# CndyShield.net
KiCad netlist of a schematic drawn in EAGLE
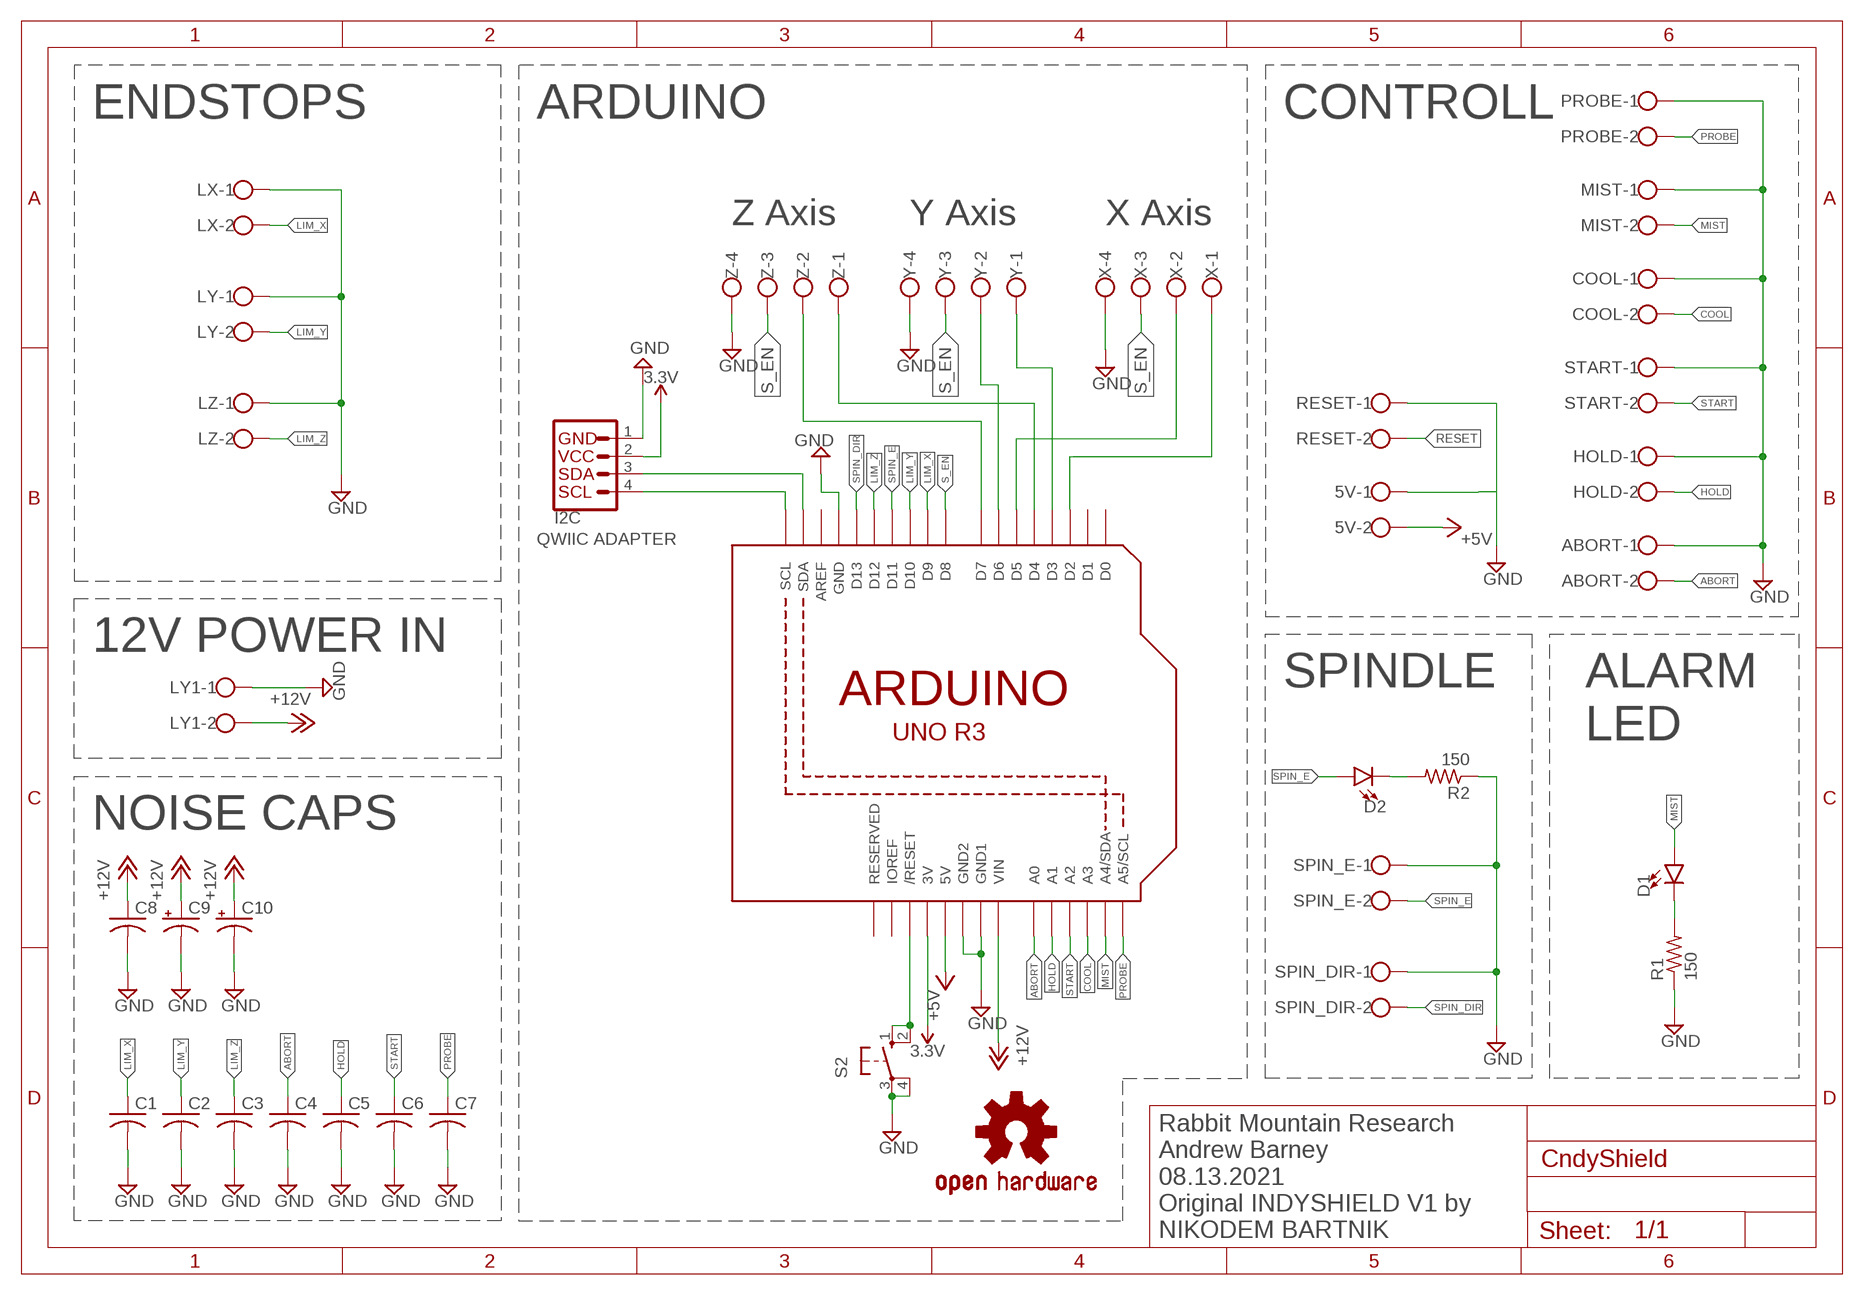
[diagram p0: schematic, sheet 1]

(export (version "E")
  (design (tool "Eeschema 10.0.6"))
  (components
    (comp (ref "5V")
      (value "W237-102")
      (footprint "eagle-import:W237-102")
      (fields (field (name "MPN") "237-102"))
      (libsource (lib "eagle-import") (part "W237-102"))
    )
    (comp (ref "ABORT")
      (value "W237-102")
      (footprint "eagle-import:W237-102")
      (fields (field (name "MPN") "237-102"))
      (libsource (lib "eagle-import") (part "W237-102"))
    )
    (comp (ref "C1")
      (value "C-US025-024X044")
      (footprint "eagle-import:C025-024X044")
      (libsource (lib "eagle-import") (part "C-US025-024X044"))
    )
    (comp (ref "C2")
      (value "C-US025-024X044")
      (footprint "eagle-import:C025-024X044")
      (libsource (lib "eagle-import") (part "C-US025-024X044"))
    )
    (comp (ref "C3")
      (value "C-US025-024X044")
      (footprint "eagle-import:C025-024X044")
      (libsource (lib "eagle-import") (part "C-US025-024X044"))
    )
    (comp (ref "C4")
      (value "C-US025-024X044")
      (footprint "eagle-import:C025-024X044")
      (libsource (lib "eagle-import") (part "C-US025-024X044"))
    )
    (comp (ref "C5")
      (value "C-US025-024X044")
      (footprint "eagle-import:C025-024X044")
      (libsource (lib "eagle-import") (part "C-US025-024X044"))
    )
    (comp (ref "C6")
      (value "C-US025-024X044")
      (footprint "eagle-import:C025-024X044")
      (libsource (lib "eagle-import") (part "C-US025-024X044"))
    )
    (comp (ref "C7")
      (value "C-US025-024X044")
      (footprint "eagle-import:C025-024X044")
      (libsource (lib "eagle-import") (part "C-US025-024X044"))
    )
    (comp (ref "C8")
      (value "C-US025-024X044")
      (footprint "eagle-import:C025-024X044")
      (libsource (lib "eagle-import") (part "C-US025-024X044"))
    )
    (comp (ref "C9")
      (value "CPOL-USE1.8-4")
      (footprint "eagle-import:E1,8-4")
      (libsource (lib "eagle-import") (part "CPOL-USE1.8-4"))
    )
    (comp (ref "C10")
      (value "CPOL-USE1.8-4")
      (footprint "eagle-import:E1,8-4")
      (libsource (lib "eagle-import") (part "CPOL-USE1.8-4"))
    )
    (comp (ref "COOL")
      (value "W237-102")
      (footprint "eagle-import:W237-102")
      (fields (field (name "MPN") "237-102"))
      (libsource (lib "eagle-import") (part "W237-102"))
    )
    (comp (ref "D1")
      (value "LED5MM")
      (footprint "eagle-import:LED_5MM")
      (libsource (lib "eagle-import") (part "LED5MM"))
    )
    (comp (ref "D2")
      (value "LED5MM")
      (footprint "eagle-import:LED_5MM")
      (libsource (lib "eagle-import") (part "LED5MM"))
    )
    (comp (ref "HOLD")
      (value "W237-102")
      (footprint "eagle-import:W237-102")
      (fields (field (name "MPN") "237-102"))
      (libsource (lib "eagle-import") (part "W237-102"))
    )
    (comp (ref "I2C")
      (value "I2C_STANDARD")
      (footprint "eagle-import:1X04")
      (libsource (lib "eagle-import") (part "I2C_STANDARD"))
    )
    (comp (ref "LOGO1")
      (value "OSHW-LOGOM")
      (footprint "eagle-import:OSHW-LOGO-M")
      (libsource (lib "eagle-import") (part "OSHW-LOGOM"))
    )
    (comp (ref "LX")
      (value "W237-102")
      (footprint "eagle-import:W237-102")
      (fields (field (name "MPN") "237-102"))
      (libsource (lib "eagle-import") (part "W237-102"))
    )
    (comp (ref "LY")
      (value "W237-102")
      (footprint "eagle-import:W237-102")
      (fields (field (name "MPN") "237-102"))
      (libsource (lib "eagle-import") (part "W237-102"))
    )
    (comp (ref "LY1")
      (value "W237-102")
      (footprint "eagle-import:W237-102")
      (fields (field (name "MPN") "237-102"))
      (libsource (lib "eagle-import") (part "W237-102"))
    )
    (comp (ref "LZ")
      (value "W237-102")
      (footprint "eagle-import:W237-102")
      (fields (field (name "MPN") "237-102"))
      (libsource (lib "eagle-import") (part "W237-102"))
    )
    (comp (ref "MIST")
      (value "W237-102")
      (footprint "eagle-import:W237-102")
      (fields (field (name "MPN") "237-102"))
      (libsource (lib "eagle-import") (part "W237-102"))
    )
    (comp (ref "PROBE")
      (value "W237-102")
      (footprint "eagle-import:W237-102")
      (fields (field (name "MPN") "237-102"))
      (libsource (lib "eagle-import") (part "W237-102"))
    )
    (comp (ref "R1")
      (value "150")
      (footprint "eagle-import:0207_10")
      (libsource (lib "eagle-import") (part "R-US_0207/10"))
    )
    (comp (ref "R2")
      (value "150")
      (footprint "eagle-import:0207_10")
      (libsource (lib "eagle-import") (part "R-US_0207/10"))
    )
    (comp (ref "RESET")
      (value "W237-102")
      (footprint "eagle-import:W237-102")
      (fields (field (name "MPN") "237-102"))
      (libsource (lib "eagle-import") (part "W237-102"))
    )
    (comp (ref "S2")
      (value "10-XX")
      (footprint "eagle-import:B3F-10XX")
      (fields (field (name "MPN") "B3F-1000"))
      (libsource (lib "eagle-import") (part "10-XX"))
    )
    (comp (ref "SPIN_DIR")
      (value "W237-102")
      (footprint "eagle-import:W237-102")
      (fields (field (name "MPN") "237-102"))
      (libsource (lib "eagle-import") (part "W237-102"))
    )
    (comp (ref "SPIN_E")
      (value "W237-102")
      (footprint "eagle-import:W237-102")
      (fields (field (name "MPN") "237-102"))
      (libsource (lib "eagle-import") (part "W237-102"))
    )
    (comp (ref "START")
      (value "W237-102")
      (footprint "eagle-import:W237-102")
      (fields (field (name "MPN") "237-102"))
      (libsource (lib "eagle-import") (part "W237-102"))
    )
    (comp (ref "U1")
      (value "ARDUINOR3-BPLACE")
      (footprint "eagle-import:ARDUINOR3-BPLACE")
      (libsource (lib "eagle-import") (part "ARDUINOR3-BPLACE"))
    )
    (comp (ref "X")
      (value "W237-4")
      (footprint "eagle-import:W237-4")
      (libsource (lib "eagle-import") (part "W237-4"))
    )
    (comp (ref "Y")
      (value "W237-4")
      (footprint "eagle-import:W237-4")
      (libsource (lib "eagle-import") (part "W237-4"))
    )
    (comp (ref "Z")
      (value "W237-4")
      (footprint "eagle-import:W237-4")
      (libsource (lib "eagle-import") (part "W237-4"))
    )
  )
  (nets
    (net (code "1") (name "+5V") (class "Default")
      (node (ref "5V") (pin "2") (pinfunction "KL_2") (pintype "passive"))
      (node (ref "U1") (pin "5V") (pinfunction "5V_5V") (pintype "power_in"))
    )
    (net (code "2") (name "+12V") (class "Default")
      (node (ref "C10") (pin "+") (pinfunction "+_+") (pintype "passive"))
      (node (ref "C8") (pin "1") (pinfunction "1_1") (pintype "passive"))
      (node (ref "C9") (pin "+") (pinfunction "+_+") (pintype "passive"))
      (node (ref "LY1") (pin "2") (pinfunction "KL_2") (pintype "passive"))
      (node (ref "U1") (pin "VIN") (pinfunction "VIN_VIN") (pintype "power_in"))
    )
    (net (code "3") (name "3.3V") (class "Default")
      (node (ref "I2C") (pin "2") (pinfunction "2_2") (pintype "power_in"))
      (node (ref "U1") (pin "3V") (pinfunction "3V_3V") (pintype "power_in"))
    )
    (net (code "4") (name "ABORT") (class "Default")
      (node (ref "ABORT") (pin "2") (pinfunction "KL_2") (pintype "passive"))
      (node (ref "C4") (pin "1") (pinfunction "1_1") (pintype "passive"))
      (node (ref "U1") (pin "A0") (pinfunction "A0_A0") (pintype "bidirectional"))
    )
    (net (code "5") (name "COOL") (class "Default")
      (node (ref "COOL") (pin "2") (pinfunction "KL_2") (pintype "passive"))
      (node (ref "U1") (pin "A3") (pinfunction "A3_A3") (pintype "bidirectional"))
    )
    (net (code "6") (name "GND") (class "Default")
      (node (ref "5V") (pin "1") (pinfunction "KL_1") (pintype "passive"))
      (node (ref "ABORT") (pin "1") (pinfunction "KL_1") (pintype "passive"))
      (node (ref "C1") (pin "2") (pinfunction "2_2") (pintype "passive"))
      (node (ref "C10") (pin "-") (pinfunction "-_-") (pintype "passive"))
      (node (ref "C2") (pin "2") (pinfunction "2_2") (pintype "passive"))
      (node (ref "C3") (pin "2") (pinfunction "2_2") (pintype "passive"))
      (node (ref "C4") (pin "2") (pinfunction "2_2") (pintype "passive"))
      (node (ref "C5") (pin "2") (pinfunction "2_2") (pintype "passive"))
      (node (ref "C6") (pin "2") (pinfunction "2_2") (pintype "passive"))
      (node (ref "C7") (pin "2") (pinfunction "2_2") (pintype "passive"))
      (node (ref "C8") (pin "2") (pinfunction "2_2") (pintype "passive"))
      (node (ref "C9") (pin "-") (pinfunction "-_-") (pintype "passive"))
      (node (ref "COOL") (pin "1") (pinfunction "KL_1") (pintype "passive"))
      (node (ref "HOLD") (pin "1") (pinfunction "KL_1") (pintype "passive"))
      (node (ref "I2C") (pin "1") (pinfunction "1_1") (pintype "power_in"))
      (node (ref "LX") (pin "1") (pinfunction "KL_1") (pintype "passive"))
      (node (ref "LY") (pin "1") (pinfunction "KL_1") (pintype "passive"))
      (node (ref "LY1") (pin "1") (pinfunction "KL_1") (pintype "passive"))
      (node (ref "LZ") (pin "1") (pinfunction "KL_1") (pintype "passive"))
      (node (ref "MIST") (pin "1") (pinfunction "KL_1") (pintype "passive"))
      (node (ref "PROBE") (pin "1") (pinfunction "KL_1") (pintype "passive"))
      (node (ref "R1") (pin "1") (pinfunction "1_1") (pintype "passive"))
      (node (ref "R2") (pin "1") (pinfunction "1_1") (pintype "passive"))
      (node (ref "RESET") (pin "1") (pinfunction "KL_1") (pintype "passive"))
      (node (ref "S2") (pin "3") (pinfunction "P_3") (pintype "passive"))
      (node (ref "S2") (pin "4") (pinfunction "P1_4") (pintype "passive"))
      (node (ref "SPIN_DIR") (pin "1") (pinfunction "KL_1") (pintype "passive"))
      (node (ref "SPIN_E") (pin "1") (pinfunction "KL_1") (pintype "passive"))
      (node (ref "START") (pin "1") (pinfunction "KL_1") (pintype "passive"))
      (node (ref "U1") (pin "GND") (pinfunction "GND_GND") (pintype "power_in"))
      (node (ref "U1") (pin "GND1") (pinfunction "GND1_GND1") (pintype "power_in"))
      (node (ref "U1") (pin "GND2") (pinfunction "GND2_GND2") (pintype "power_in"))
      (node (ref "X") (pin "4") (pinfunction "KL_4") (pintype "passive"))
      (node (ref "Y") (pin "4") (pinfunction "KL_4") (pintype "passive"))
      (node (ref "Z") (pin "4") (pinfunction "KL_4") (pintype "passive"))
    )
    (net (code "7") (name "HOLD") (class "Default")
      (node (ref "C5") (pin "1") (pinfunction "1_1") (pintype "passive"))
      (node (ref "HOLD") (pin "2") (pinfunction "KL_2") (pintype "passive"))
      (node (ref "U1") (pin "A1") (pinfunction "A1_A1") (pintype "bidirectional"))
    )
    (net (code "8") (name "LIM_X") (class "Default")
      (node (ref "C1") (pin "1") (pinfunction "1_1") (pintype "passive"))
      (node (ref "LX") (pin "2") (pinfunction "KL_2") (pintype "passive"))
      (node (ref "U1") (pin "D9") (pinfunction "D9_D9") (pintype "bidirectional"))
    )
    (net (code "9") (name "LIM_Y") (class "Default")
      (node (ref "C2") (pin "1") (pinfunction "1_1") (pintype "passive"))
      (node (ref "LY") (pin "2") (pinfunction "KL_2") (pintype "passive"))
      (node (ref "U1") (pin "D10") (pinfunction "D10_D10") (pintype "bidirectional"))
    )
    (net (code "10") (name "LIM_Z") (class "Default")
      (node (ref "C3") (pin "1") (pinfunction "1_1") (pintype "passive"))
      (node (ref "LZ") (pin "2") (pinfunction "KL_2") (pintype "passive"))
      (node (ref "U1") (pin "D12") (pinfunction "D12_D12") (pintype "bidirectional"))
    )
    (net (code "11") (name "MIST") (class "Default")
      (node (ref "D1") (pin "A") (pinfunction "A_A") (pintype "passive"))
      (node (ref "MIST") (pin "2") (pinfunction "KL_2") (pintype "passive"))
      (node (ref "U1") (pin "A4") (pinfunction "A4/SDA_A4") (pintype "bidirectional"))
    )
    (net (code "12") (name "Net-(D1-C)") (class "Default")
      (node (ref "D1") (pin "K") (pinfunction "C_K") (pintype "passive"))
      (node (ref "R1") (pin "2") (pinfunction "2_2") (pintype "passive"))
    )
    (net (code "13") (name "Net-(D2-C)") (class "Default")
      (node (ref "D2") (pin "K") (pinfunction "C_K") (pintype "passive"))
      (node (ref "R2") (pin "2") (pinfunction "2_2") (pintype "passive"))
    )
    (net (code "14") (name "Net-(I2C-Pad3)") (class "Default")
      (node (ref "I2C") (pin "3") (pinfunction "3_3") (pintype "passive"))
      (node (ref "U1") (pin "SDA") (pinfunction "SDA_SDA") (pintype "bidirectional"))
    )
    (net (code "15") (name "Net-(I2C-Pad4)") (class "Default")
      (node (ref "I2C") (pin "4") (pinfunction "4_4") (pintype "passive"))
      (node (ref "U1") (pin "SCL") (pinfunction "SCL_SCL") (pintype "bidirectional"))
    )
    (net (code "16") (name "Net-(XA-KL)") (class "Default")
      (node (ref "U1") (pin "D2") (pinfunction "D2_D2") (pintype "bidirectional"))
      (node (ref "X") (pin "1") (pinfunction "KL_1") (pintype "passive"))
    )
    (net (code "17") (name "Net-(XB-KL)") (class "Default")
      (node (ref "U1") (pin "D5") (pinfunction "D5_D5") (pintype "bidirectional"))
      (node (ref "X") (pin "2") (pinfunction "KL_2") (pintype "passive"))
    )
    (net (code "18") (name "Net-(YA-KL)") (class "Default")
      (node (ref "U1") (pin "D3") (pinfunction "D3_D3") (pintype "bidirectional"))
      (node (ref "Y") (pin "1") (pinfunction "KL_1") (pintype "passive"))
    )
    (net (code "19") (name "Net-(YB-KL)") (class "Default")
      (node (ref "U1") (pin "D6") (pinfunction "D6_D6") (pintype "bidirectional"))
      (node (ref "Y") (pin "2") (pinfunction "KL_2") (pintype "passive"))
    )
    (net (code "20") (name "Net-(ZA-KL)") (class "Default")
      (node (ref "U1") (pin "D4") (pinfunction "D4_D4") (pintype "bidirectional"))
      (node (ref "Z") (pin "1") (pinfunction "KL_1") (pintype "passive"))
    )
    (net (code "21") (name "Net-(ZB-KL)") (class "Default")
      (node (ref "U1") (pin "D7") (pinfunction "D7_D7") (pintype "bidirectional"))
      (node (ref "Z") (pin "2") (pinfunction "KL_2") (pintype "passive"))
    )
    (net (code "22") (name "PROBE") (class "Default")
      (node (ref "C7") (pin "1") (pinfunction "1_1") (pintype "passive"))
      (node (ref "PROBE") (pin "2") (pinfunction "KL_2") (pintype "passive"))
      (node (ref "U1") (pin "A5") (pinfunction "A5/SCL_A5") (pintype "bidirectional"))
    )
    (net (code "23") (name "RESET") (class "Default")
      (node (ref "RESET") (pin "2") (pinfunction "KL_2") (pintype "passive"))
      (node (ref "S2") (pin "1") (pinfunction "S_1") (pintype "passive"))
      (node (ref "S2") (pin "2") (pinfunction "S1_2") (pintype "passive"))
      (node (ref "U1") (pin "RESET") (pinfunction "/RESET_RESET") (pintype "bidirectional"))
    )
    (net (code "24") (name "SPIN_DIR") (class "Default")
      (node (ref "SPIN_DIR") (pin "2") (pinfunction "KL_2") (pintype "passive"))
      (node (ref "U1") (pin "D13") (pinfunction "D13_D13") (pintype "bidirectional"))
    )
    (net (code "25") (name "SPIN_E") (class "Default")
      (node (ref "D2") (pin "A") (pinfunction "A_A") (pintype "passive"))
      (node (ref "SPIN_E") (pin "2") (pinfunction "KL_2") (pintype "passive"))
      (node (ref "U1") (pin "D11") (pinfunction "D11_D11") (pintype "bidirectional"))
    )
    (net (code "26") (name "START") (class "Default")
      (node (ref "C6") (pin "1") (pinfunction "1_1") (pintype "passive"))
      (node (ref "START") (pin "2") (pinfunction "KL_2") (pintype "passive"))
      (node (ref "U1") (pin "A2") (pinfunction "A2_A2") (pintype "bidirectional"))
    )
    (net (code "27") (name "S_EN") (class "Default")
      (node (ref "U1") (pin "D8") (pinfunction "D8_D8") (pintype "bidirectional"))
      (node (ref "X") (pin "3") (pinfunction "KL_3") (pintype "passive"))
      (node (ref "Y") (pin "3") (pinfunction "KL_3") (pintype "passive"))
      (node (ref "Z") (pin "3") (pinfunction "KL_3") (pintype "passive"))
    )
    (net (code "28") (name "unconnected-(U1-PadAREF)") (class "Default")
      (node (ref "U1") (pin "AREF") (pinfunction "AREF_AREF") (pintype "bidirectional"))
    )
    (net (code "29") (name "unconnected-(U1-PadD0)") (class "Default")
      (node (ref "U1") (pin "D0") (pinfunction "D0_D0") (pintype "bidirectional"))
    )
    (net (code "30") (name "unconnected-(U1-PadD1)") (class "Default")
      (node (ref "U1") (pin "D1") (pinfunction "D1_D1") (pintype "bidirectional"))
    )
    (net (code "31") (name "unconnected-(U1-PadIOREF)") (class "Default")
      (node (ref "U1") (pin "IOREF") (pinfunction "IOREF_IOREF") (pintype "output"))
    )
    (net (code "32") (name "unconnected-(U1-PadRESERVED)") (class "Default")
      (node (ref "U1") (pin "RESERVED") (pinfunction "RESERVED_RESERVED") (pintype "no_connect"))
    )
  )
)
